# UNI_1_1.net
KiCad netlist of a schematic drawn in EAGLE
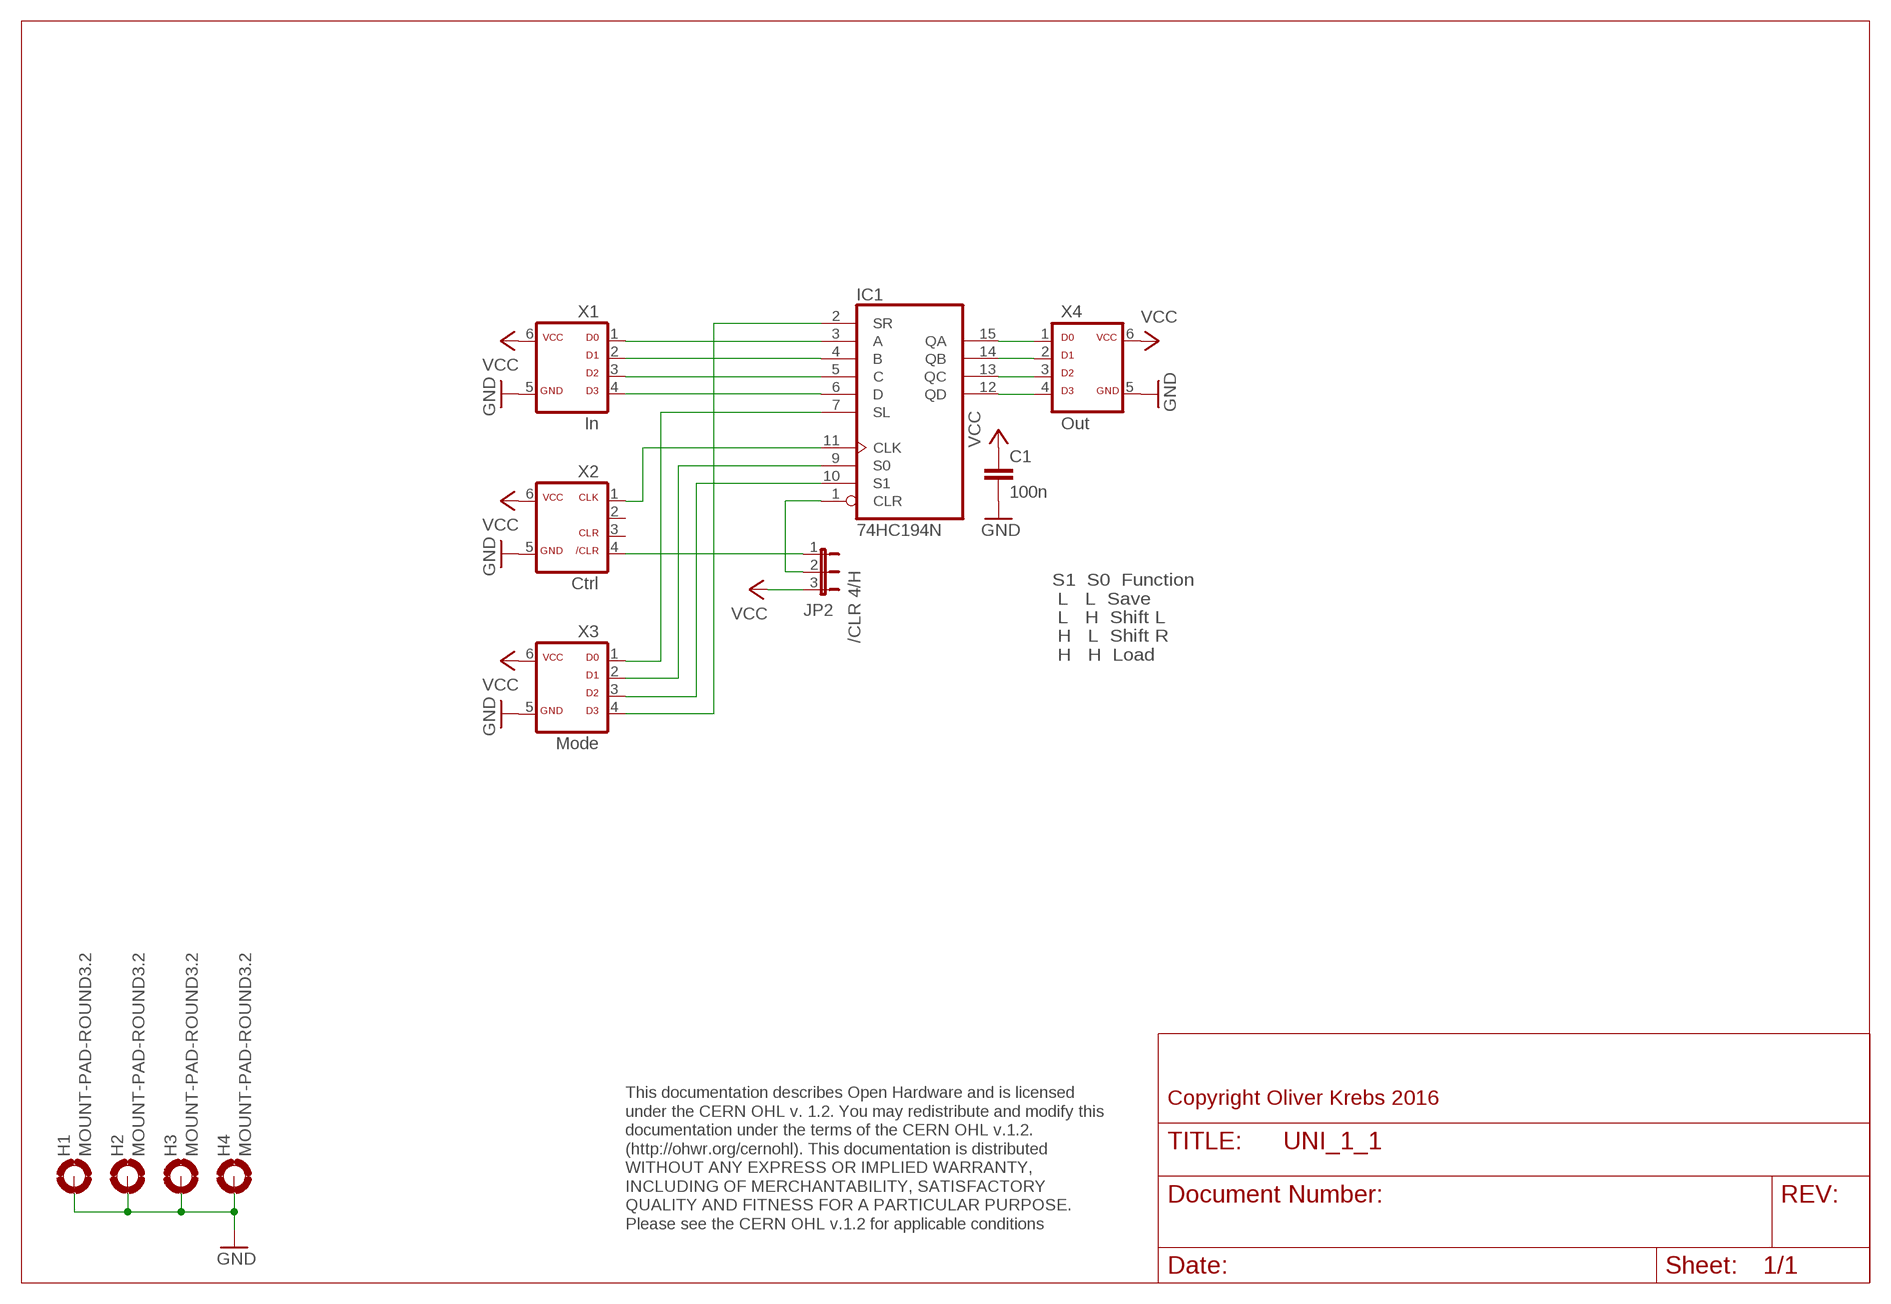
[diagram p0: schematic, sheet 1]

(export (version "E")
  (design (tool "Eeschema 10.0.6"))
  (components
    (comp (ref "C1")
      (value "100n")
      (footprint "eagle-import:C050-025X075")
      (libsource (lib "eagle-import") (part "C-EU050-025X075"))
    )
    (comp (ref "H1")
      (value "MOUNT-PAD-ROUND3.2")
      (footprint "eagle-import:3,2-PAD")
      (libsource (lib "eagle-import") (part "MOUNT-PAD-ROUND3.2"))
    )
    (comp (ref "H2")
      (value "MOUNT-PAD-ROUND3.2")
      (footprint "eagle-import:3,2-PAD")
      (libsource (lib "eagle-import") (part "MOUNT-PAD-ROUND3.2"))
    )
    (comp (ref "H3")
      (value "MOUNT-PAD-ROUND3.2")
      (footprint "eagle-import:3,2-PAD")
      (libsource (lib "eagle-import") (part "MOUNT-PAD-ROUND3.2"))
    )
    (comp (ref "H4")
      (value "MOUNT-PAD-ROUND3.2")
      (footprint "eagle-import:3,2-PAD")
      (libsource (lib "eagle-import") (part "MOUNT-PAD-ROUND3.2"))
    )
    (comp (ref "IC1")
      (value "74HC194N")
      (footprint "eagle-import:DIL16")
      (libsource (lib "eagle-import") (part "74194NHC"))
    )
    (comp (ref "JP2")
      (value "/CLR 4/H")
      (footprint "eagle-import:JP2")
      (libsource (lib "eagle-import") (part "JP2E"))
    )
    (comp (ref "X1")
      (value "In")
      (footprint "eagle-import:ML-6")
      (libsource (lib "eagle-import") (part "ML6D"))
    )
    (comp (ref "X2")
      (value "Ctrl")
      (footprint "eagle-import:ML-6")
      (libsource (lib "eagle-import") (part "ML6C"))
    )
    (comp (ref "X3")
      (value "Mode")
      (footprint "eagle-import:ML-6")
      (libsource (lib "eagle-import") (part "ML6D"))
    )
    (comp (ref "X4")
      (value "Out")
      (footprint "eagle-import:ML-6")
      (libsource (lib "eagle-import") (part "ML6D"))
    )
  )
  (nets
    (net (code "1") (name "GND") (class "Default")
      (node (ref "C1") (pin "2") (pinfunction "2_2") (pintype "passive"))
      (node (ref "H1") (pin "B3,2") (pinfunction "MOUNT_B3,2") (pintype "passive"))
      (node (ref "H2") (pin "B3,2") (pinfunction "MOUNT_B3,2") (pintype "passive"))
      (node (ref "H3") (pin "B3,2") (pinfunction "MOUNT_B3,2") (pintype "passive"))
      (node (ref "H4") (pin "B3,2") (pinfunction "MOUNT_B3,2") (pintype "passive"))
      (node (ref "X1") (pin "5") (pinfunction "5_5") (pintype "passive"))
      (node (ref "X2") (pin "5") (pinfunction "5_5") (pintype "passive"))
      (node (ref "X3") (pin "5") (pinfunction "5_5") (pintype "passive"))
      (node (ref "X4") (pin "5") (pinfunction "5_5") (pintype "passive"))
    )
    (net (code "2") (name "Net-(IC1A-A)") (class "Default")
      (node (ref "IC1") (pin "3") (pinfunction "A_3") (pintype "input"))
      (node (ref "X1") (pin "1") (pinfunction "1_1") (pintype "passive"))
    )
    (net (code "3") (name "Net-(IC1A-B)") (class "Default")
      (node (ref "IC1") (pin "4") (pinfunction "B_4") (pintype "input"))
      (node (ref "X1") (pin "2") (pinfunction "2_2") (pintype "passive"))
    )
    (net (code "4") (name "Net-(IC1A-C)") (class "Default")
      (node (ref "IC1") (pin "5") (pinfunction "C_5") (pintype "input"))
      (node (ref "X1") (pin "3") (pinfunction "3_3") (pintype "passive"))
    )
    (net (code "5") (name "Net-(IC1A-CLK)") (class "Default")
      (node (ref "IC1") (pin "11") (pinfunction "CLK_11") (pintype "input"))
      (node (ref "X2") (pin "1") (pinfunction "1_1") (pintype "passive"))
    )
    (net (code "6") (name "Net-(IC1A-CLR)") (class "Default")
      (node (ref "IC1") (pin "1") (pinfunction "CLR_1") (pintype "input"))
      (node (ref "JP2") (pin "2") (pinfunction "2_2") (pintype "passive"))
    )
    (net (code "7") (name "Net-(IC1A-D)") (class "Default")
      (node (ref "IC1") (pin "6") (pinfunction "D_6") (pintype "input"))
      (node (ref "X1") (pin "4") (pinfunction "4_4") (pintype "passive"))
    )
    (net (code "8") (name "Net-(IC1A-QA)") (class "Default")
      (node (ref "IC1") (pin "15") (pinfunction "QA_15") (pintype "output"))
      (node (ref "X4") (pin "1") (pinfunction "1_1") (pintype "passive"))
    )
    (net (code "9") (name "Net-(IC1A-QB)") (class "Default")
      (node (ref "IC1") (pin "14") (pinfunction "QB_14") (pintype "output"))
      (node (ref "X4") (pin "2") (pinfunction "2_2") (pintype "passive"))
    )
    (net (code "10") (name "Net-(IC1A-QC)") (class "Default")
      (node (ref "IC1") (pin "13") (pinfunction "QC_13") (pintype "output"))
      (node (ref "X4") (pin "3") (pinfunction "3_3") (pintype "passive"))
    )
    (net (code "11") (name "Net-(IC1A-QD)") (class "Default")
      (node (ref "IC1") (pin "12") (pinfunction "QD_12") (pintype "output"))
      (node (ref "X4") (pin "4") (pinfunction "4_4") (pintype "passive"))
    )
    (net (code "12") (name "Net-(IC1A-S0)") (class "Default")
      (node (ref "IC1") (pin "9") (pinfunction "S0_9") (pintype "input"))
      (node (ref "X3") (pin "2") (pinfunction "2_2") (pintype "passive"))
    )
    (net (code "13") (name "Net-(IC1A-S1)") (class "Default")
      (node (ref "IC1") (pin "10") (pinfunction "S1_10") (pintype "input"))
      (node (ref "X3") (pin "3") (pinfunction "3_3") (pintype "passive"))
    )
    (net (code "14") (name "Net-(IC1A-SL)") (class "Default")
      (node (ref "IC1") (pin "7") (pinfunction "SL_7") (pintype "input"))
      (node (ref "X3") (pin "1") (pinfunction "1_1") (pintype "passive"))
    )
    (net (code "15") (name "Net-(IC1A-SR)") (class "Default")
      (node (ref "IC1") (pin "2") (pinfunction "SR_2") (pintype "input"))
      (node (ref "X3") (pin "4") (pinfunction "4_4") (pintype "passive"))
    )
    (net (code "16") (name "Net-(JP2-Pad1)") (class "Default")
      (node (ref "JP2") (pin "1") (pinfunction "1_1") (pintype "passive"))
      (node (ref "X2") (pin "4") (pinfunction "4_4") (pintype "passive"))
    )
    (net (code "17") (name "VCC") (class "Default")
      (node (ref "C1") (pin "1") (pinfunction "1_1") (pintype "passive"))
      (node (ref "JP2") (pin "3") (pinfunction "3_3") (pintype "passive"))
      (node (ref "X1") (pin "6") (pinfunction "6_6") (pintype "passive"))
      (node (ref "X2") (pin "6") (pinfunction "6_6") (pintype "passive"))
      (node (ref "X3") (pin "6") (pinfunction "6_6") (pintype "passive"))
      (node (ref "X4") (pin "6") (pinfunction "6_6") (pintype "passive"))
    )
    (net (code "18") (name "unconnected-(X2-Pad2)") (class "Default")
      (node (ref "X2") (pin "2") (pinfunction "2_2") (pintype "passive"))
    )
    (net (code "19") (name "unconnected-(X2-Pad3)") (class "Default")
      (node (ref "X2") (pin "3") (pinfunction "3_3") (pintype "passive"))
    )
  )
)
